# microbit-v2-smart-robot-schematic-2023-0.net
KiCad netlist of a schematic drawn in EasyEDA
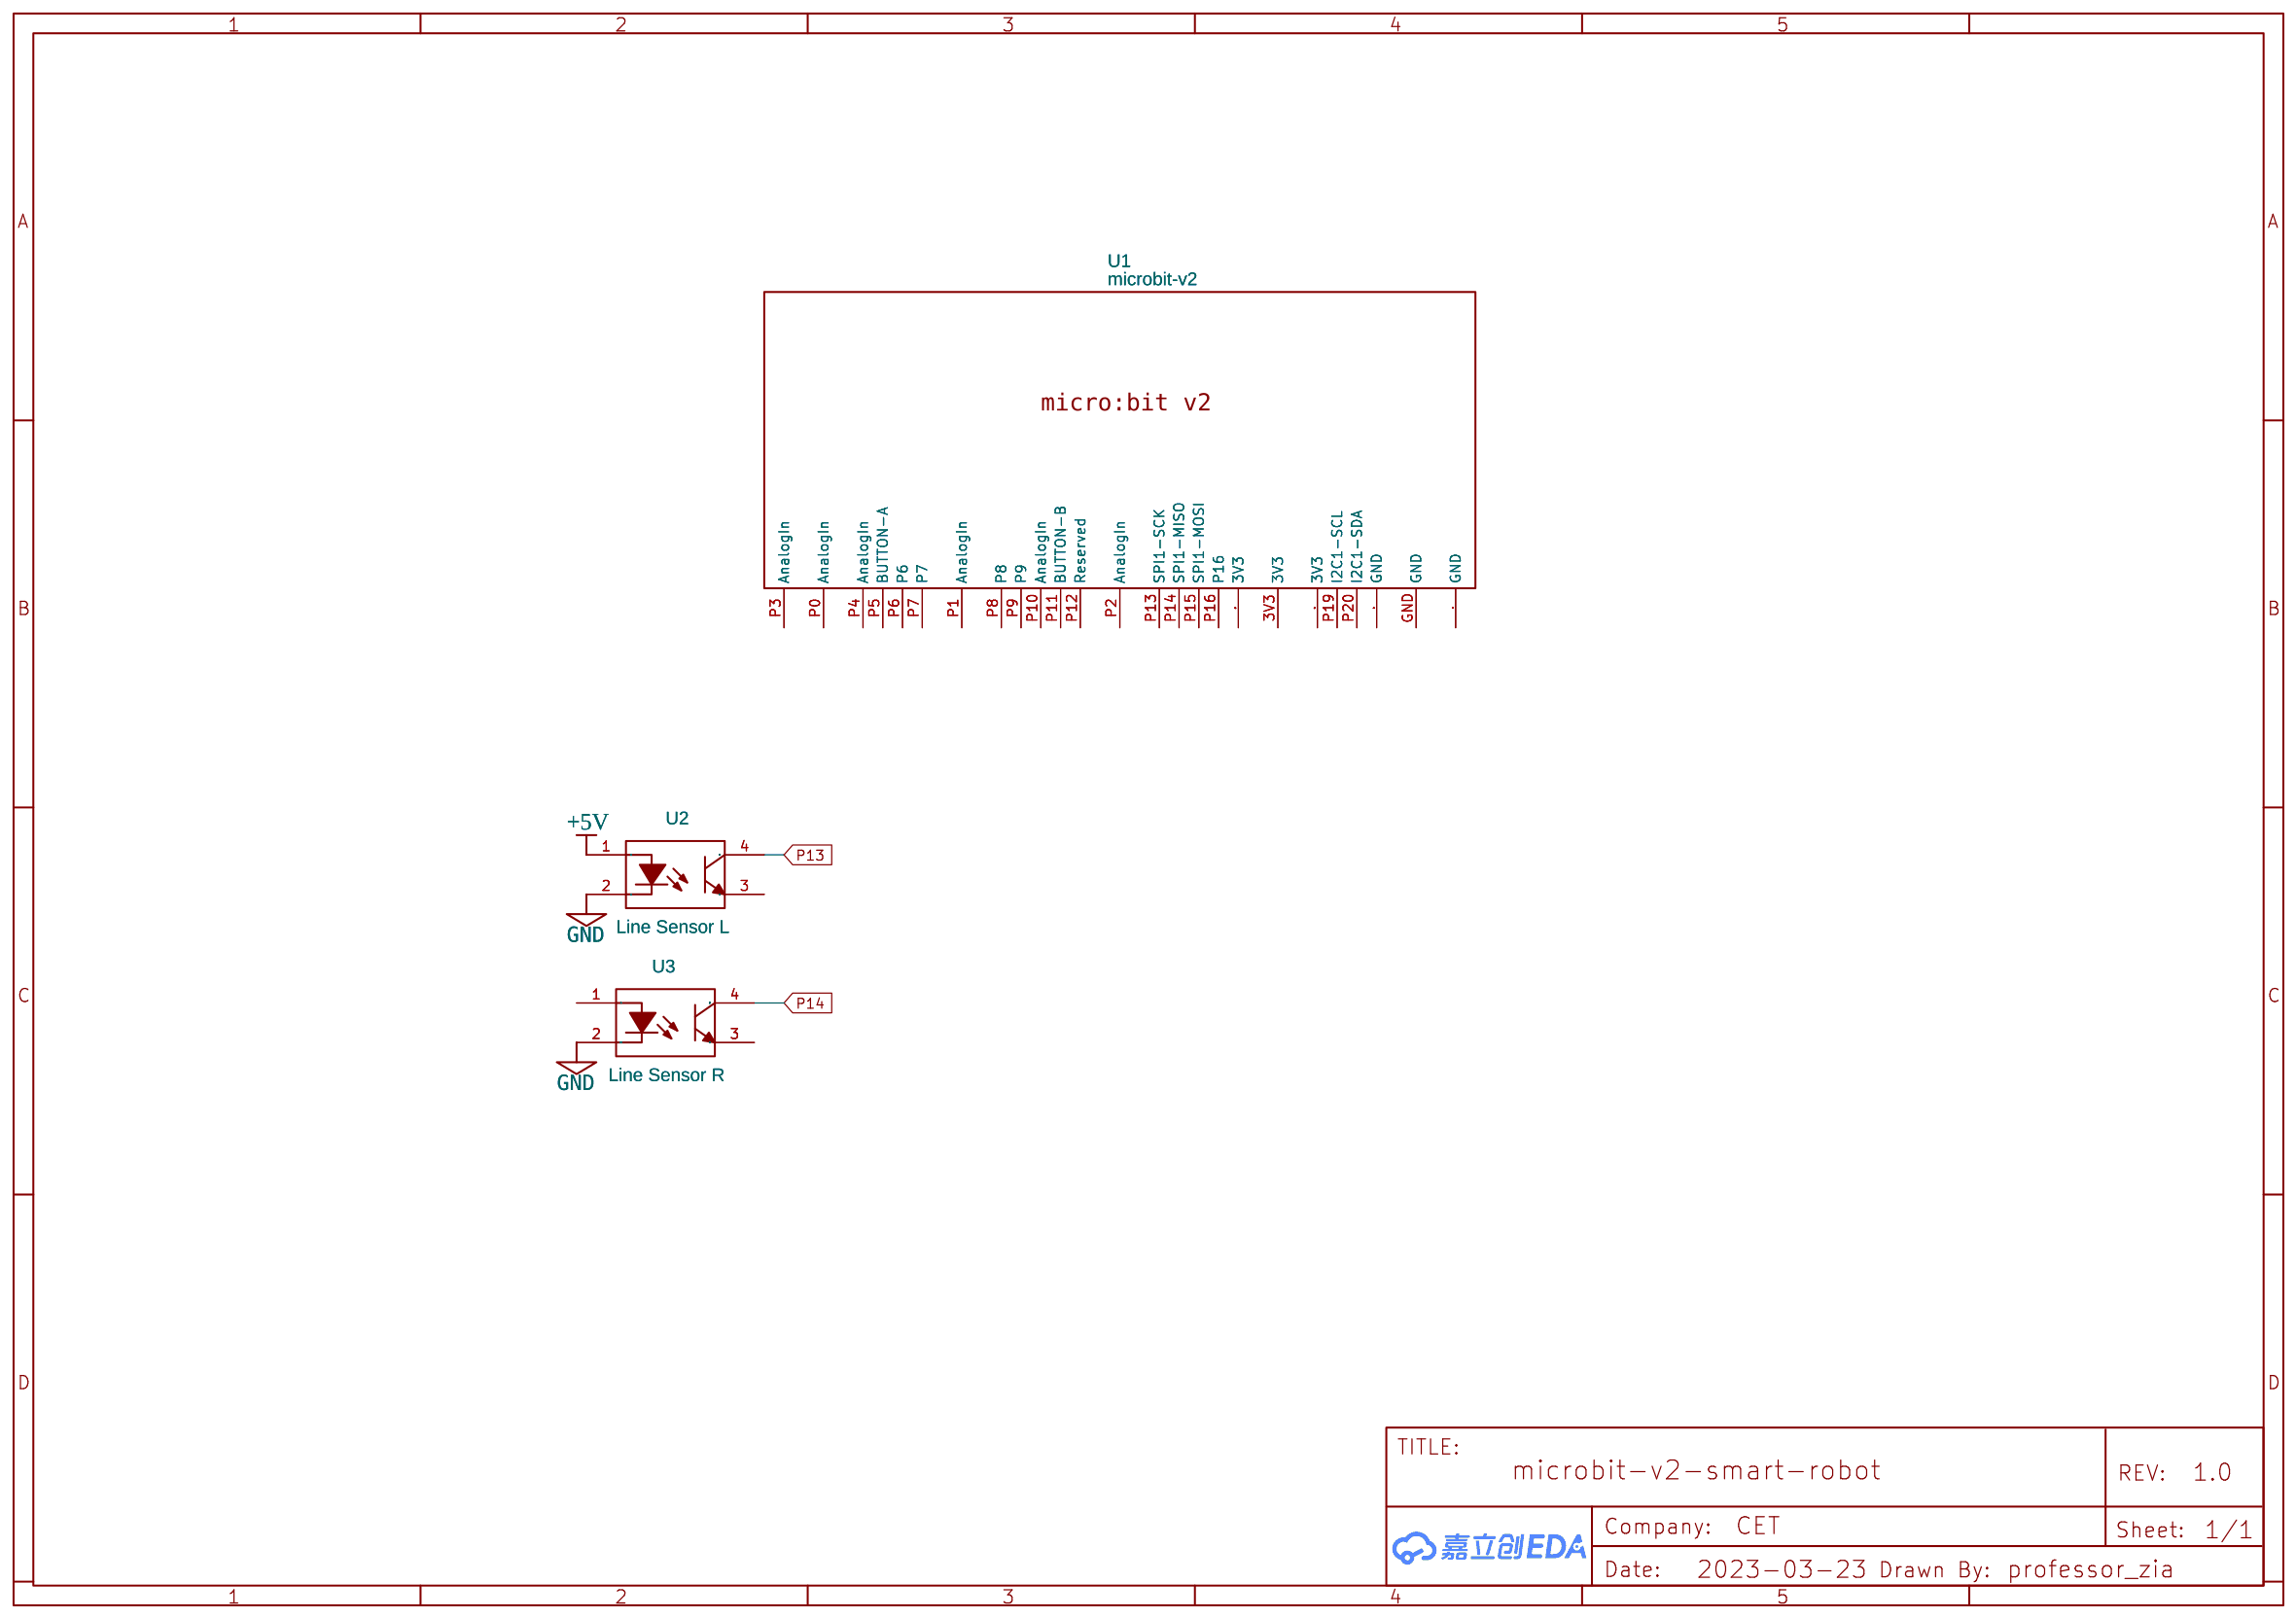
[diagram p0: schematic sheet]

(export (version "E")
  (design (tool "Eeschema 10.0.6"))
  (components
    (comp (ref "U1") (value "microbit-v2") (libsource (lib "") (part "microbit-v2")))
    (comp (ref "U2")
      (value "Line Sensor L")
      (fields
        (field (name "BOM_Manufacturer Part") "TLP291(GB-TP,SE(O")
        (field (name "BOM_Supplier Part") "C393895")
      )
      (libsource (lib "") (part "TLP291(GB-TP,SE(O"))
    )
    (comp (ref "U3")
      (value "Line Sensor R")
      (fields
        (field (name "BOM_Manufacturer Part") "TLP291(GB-TP,SE(O")
        (field (name "BOM_Supplier Part") "C393895")
      )
      (libsource (lib "") (part "TLP291(GB-TP,SE(O"))
    )
  )
  (nets
    (net (code "1") (name "+5V") (class "Default")
      (node (ref "U2") (pin "1") (pinfunction "AN_1") (pintype "unspecified"))
    )
    (net (code "2") (name "GND") (class "Default")
      (node (ref "U2") (pin "2") (pinfunction "CAT_2") (pintype "unspecified"))
      (node (ref "U3") (pin "2") (pinfunction "CAT_2") (pintype "unspecified"))
    )
    (net (code "3") (name "P13") (class "Default")
      (node (ref "U2") (pin "4") (pinfunction "COL_4") (pintype "unspecified"))
    )
    (net (code "4") (name "P14") (class "Default")
      (node (ref "U3") (pin "4") (pinfunction "COL_4") (pintype "unspecified"))
    )
    (net (code "5") (name "unconnected-(U1-3V3-Pad3Va)") (class "Default")
      (node (ref "U1") (pin "3Va") (pinfunction "3V3_3Va") (pintype "unspecified"))
    )
    (net (code "6") (name "unconnected-(U1-3V3-Pad3Vb)") (class "Default")
      (node (ref "U1") (pin "3Vb") (pinfunction "3V3_3Vb") (pintype "unspecified"))
    )
    (net (code "7") (name "unconnected-(U1-AnalogIn-PadP0)") (class "Default")
      (node (ref "U1") (pin "P0") (pinfunction "AnalogIn_P0") (pintype "unspecified"))
    )
    (net (code "8") (name "unconnected-(U1-AnalogIn-PadP1)") (class "Default")
      (node (ref "U1") (pin "P1") (pinfunction "AnalogIn_P1") (pintype "unspecified"))
    )
    (net (code "9") (name "unconnected-(U1-AnalogIn-PadP2)") (class "Default")
      (node (ref "U1") (pin "P2") (pinfunction "AnalogIn_P2") (pintype "unspecified"))
    )
    (net (code "10") (name "unconnected-(U1-AnalogIn-PadP3)") (class "Default")
      (node (ref "U1") (pin "P3") (pinfunction "AnalogIn_P3") (pintype "unspecified"))
    )
    (net (code "11") (name "unconnected-(U1-AnalogIn-PadP4)") (class "Default")
      (node (ref "U1") (pin "P4") (pinfunction "AnalogIn_P4") (pintype "unspecified"))
    )
    (net (code "12") (name "unconnected-(U1-AnalogIn-PadP10)") (class "Default")
      (node (ref "U1") (pin "P10") (pinfunction "AnalogIn_P10") (pintype "unspecified"))
    )
    (net (code "13") (name "unconnected-(U1-BUTTON-A-PadP5)") (class "Default")
      (node (ref "U1") (pin "P5") (pinfunction "BUTTON-A_P5") (pintype "unspecified"))
    )
    (net (code "14") (name "unconnected-(U1-BUTTON-B-PadP11)") (class "Default")
      (node (ref "U1") (pin "P11") (pinfunction "BUTTON-B_P11") (pintype "unspecified"))
    )
    (net (code "15") (name "unconnected-(U1-GND-PadGa)") (class "Default")
      (node (ref "U1") (pin "Ga") (pinfunction "GND_Ga") (pintype "unspecified"))
    )
    (net (code "16") (name "unconnected-(U1-GND-PadGb)") (class "Default")
      (node (ref "U1") (pin "Gb") (pinfunction "GND_Gb") (pintype "unspecified"))
    )
    (net (code "17") (name "unconnected-(U1-I2C1-SCL-PadP19)") (class "Default")
      (node (ref "U1") (pin "P19") (pinfunction "I2C1-SCL_P19") (pintype "unspecified"))
    )
    (net (code "18") (name "unconnected-(U1-I2C1-SDA-PadP20)") (class "Default")
      (node (ref "U1") (pin "P20") (pinfunction "I2C1-SDA_P20") (pintype "unspecified"))
    )
    (net (code "19") (name "unconnected-(U1-Pad3V3)") (class "Default")
      (node (ref "U1") (pin "3V3") (pinfunction "3V3_3V3") (pintype "unspecified"))
    )
    (net (code "20") (name "unconnected-(U1-PadGND)") (class "Default")
      (node (ref "U1") (pin "GND") (pinfunction "GND_GND") (pintype "unspecified"))
    )
    (net (code "21") (name "unconnected-(U1-PadP6)") (class "Default")
      (node (ref "U1") (pin "P6") (pinfunction "P6_P6") (pintype "unspecified"))
    )
    (net (code "22") (name "unconnected-(U1-PadP7)") (class "Default")
      (node (ref "U1") (pin "P7") (pinfunction "P7_P7") (pintype "unspecified"))
    )
    (net (code "23") (name "unconnected-(U1-PadP8)") (class "Default")
      (node (ref "U1") (pin "P8") (pinfunction "P8_P8") (pintype "unspecified"))
    )
    (net (code "24") (name "unconnected-(U1-PadP9)") (class "Default")
      (node (ref "U1") (pin "P9") (pinfunction "P9_P9") (pintype "unspecified"))
    )
    (net (code "25") (name "unconnected-(U1-PadP16)") (class "Default")
      (node (ref "U1") (pin "P16") (pinfunction "P16_P16") (pintype "unspecified"))
    )
    (net (code "26") (name "unconnected-(U1-Reserved-PadP12)") (class "Default")
      (node (ref "U1") (pin "P12") (pinfunction "Reserved_P12") (pintype "unspecified"))
    )
    (net (code "27") (name "unconnected-(U1-SPI1-MISO-PadP14)") (class "Default")
      (node (ref "U1") (pin "P14") (pinfunction "SPI1-MISO_P14") (pintype "unspecified"))
    )
    (net (code "28") (name "unconnected-(U1-SPI1-MOSI-PadP15)") (class "Default")
      (node (ref "U1") (pin "P15") (pinfunction "SPI1-MOSI_P15") (pintype "unspecified"))
    )
    (net (code "29") (name "unconnected-(U1-SPI1-SCK-PadP13)") (class "Default")
      (node (ref "U1") (pin "P13") (pinfunction "SPI1-SCK_P13") (pintype "unspecified"))
    )
    (net (code "30") (name "unconnected-(U2-EM-Pad3)") (class "Default")
      (node (ref "U2") (pin "3") (pinfunction "EM_3") (pintype "unspecified"))
    )
    (net (code "31") (name "unconnected-(U3-AN-Pad1)") (class "Default")
      (node (ref "U3") (pin "1") (pinfunction "AN_1") (pintype "unspecified"))
    )
    (net (code "32") (name "unconnected-(U3-EM-Pad3)") (class "Default")
      (node (ref "U3") (pin "3") (pinfunction "EM_3") (pintype "unspecified"))
    )
  )
)
